# AdaptI2C-RF.net
KiCad netlist of a schematic drawn in EAGLE
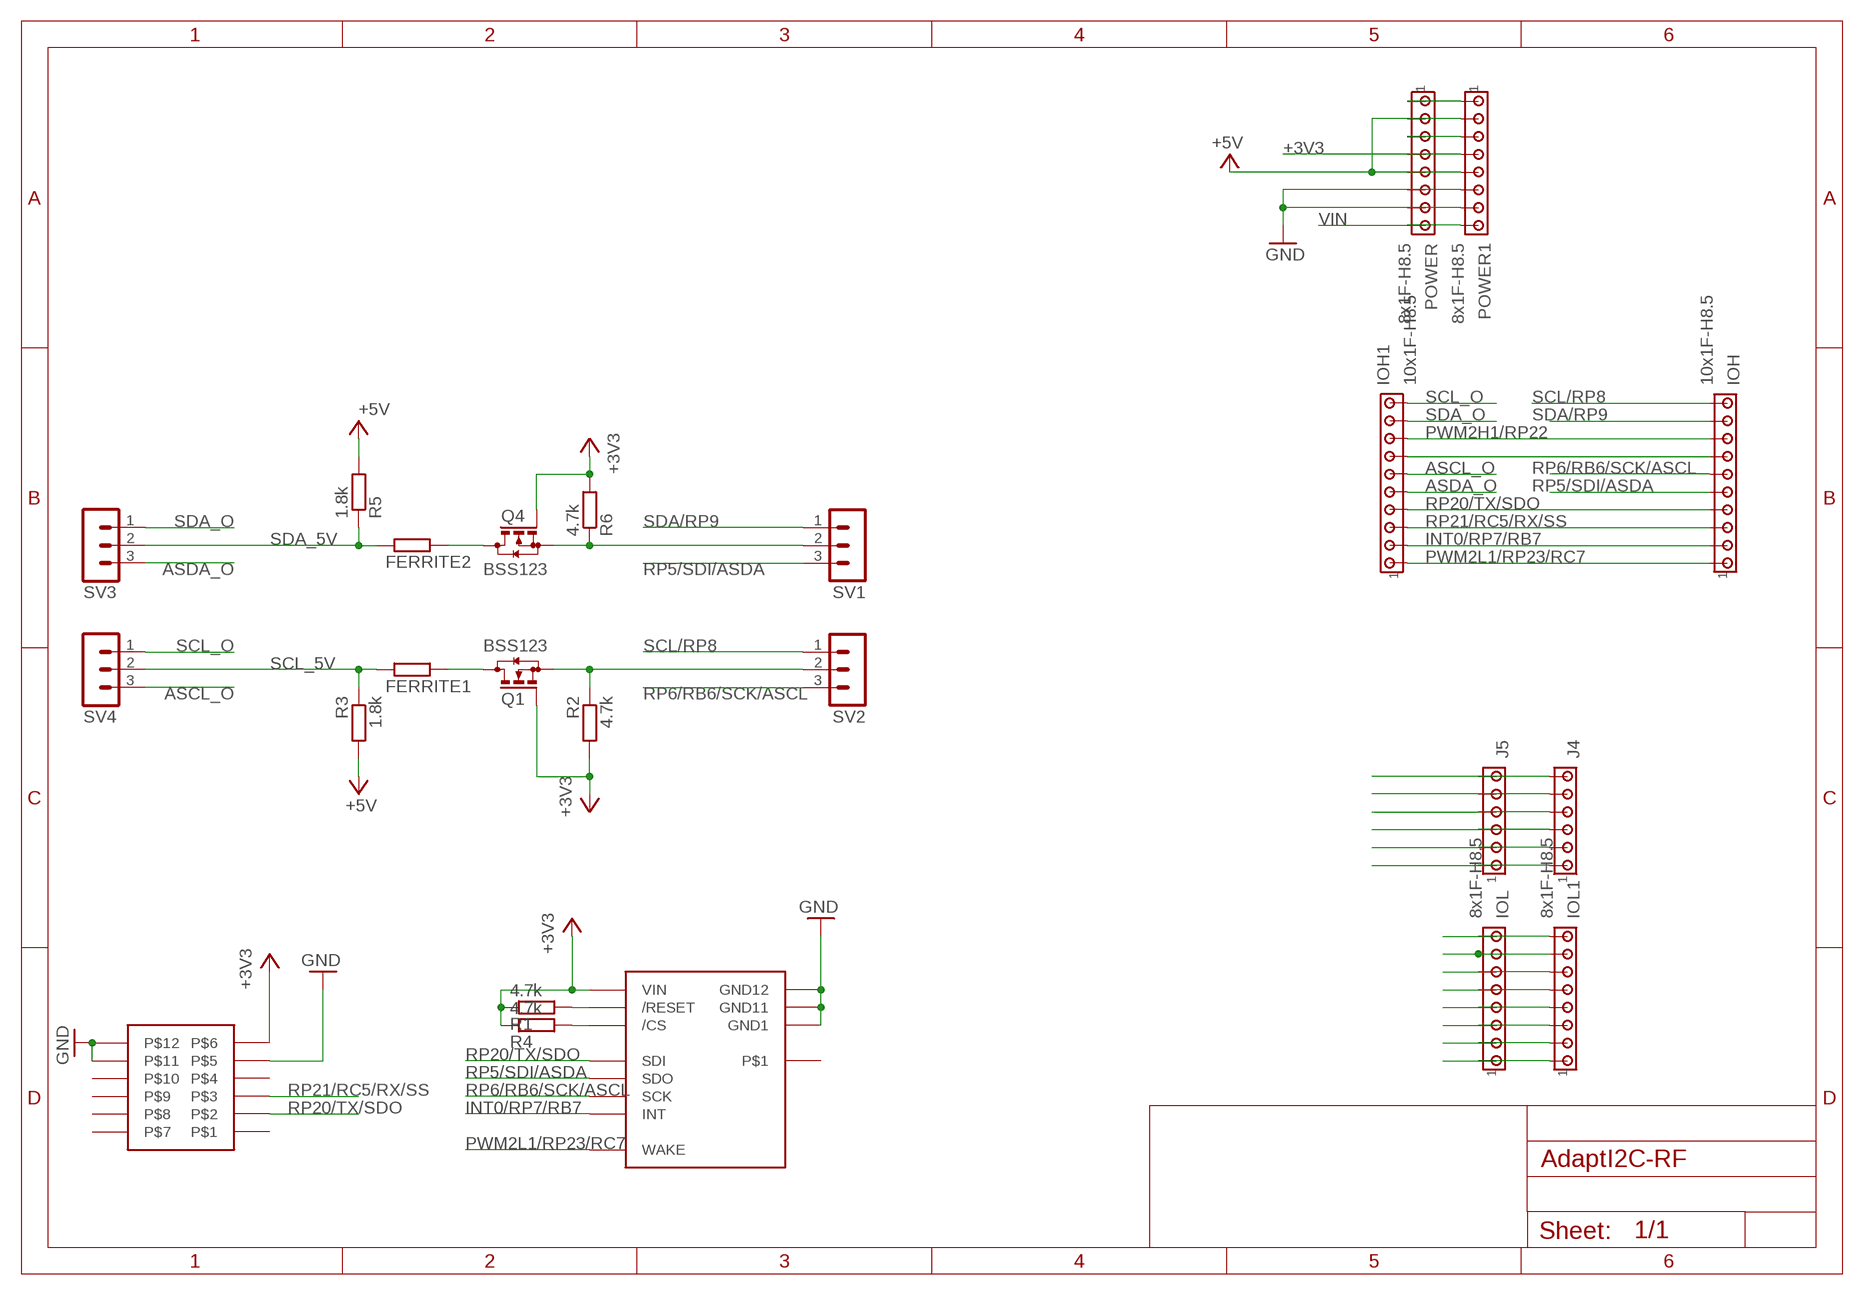
[diagram p0: schematic, sheet 1]

(export (version "E")
  (design (tool "Eeschema 10.0.6"))
  (components
    (comp (ref "FERRITE1")
      (value "R-EU_M0805")
      (footprint "eagle-import:M0805")
      (libsource (lib "eagle-import") (part "R-EU_M0805"))
    )
    (comp (ref "FERRITE2")
      (value "R-EU_M0805")
      (footprint "eagle-import:M0805")
      (libsource (lib "eagle-import") (part "R-EU_M0805"))
    )
    (comp (ref "IOH")
      (value "10x1F-H8.5")
      (footprint "eagle-import:10X10MTA")
      (libsource (lib "eagle-import") (part "MTA10-100"))
    )
    (comp (ref "IOH1")
      (value "10x1F-H8.5")
      (footprint "eagle-import:10X10MTA")
      (libsource (lib "eagle-import") (part "MTA10-100"))
    )
    (comp (ref "IOL")
      (value "8x1F-H8.5")
      (footprint "eagle-import:10X08MTA")
      (libsource (lib "eagle-import") (part "MTA08-100"))
    )
    (comp (ref "IOL1")
      (value "8x1F-H8.5")
      (footprint "eagle-import:10X08MTA")
      (libsource (lib "eagle-import") (part "MTA08-100"))
    )
    (comp (ref "J4")
      (value "MTA06-100")
      (footprint "eagle-import:10X06MTA")
      (libsource (lib "eagle-import") (part "MTA06-100"))
    )
    (comp (ref "J5")
      (value "MTA06-100")
      (footprint "eagle-import:10X06MTA")
      (libsource (lib "eagle-import") (part "MTA06-100"))
    )
    (comp (ref "POWER")
      (value "8x1F-H8.5")
      (footprint "eagle-import:10X08MTA")
      (libsource (lib "eagle-import") (part "MTA08-100"))
    )
    (comp (ref "POWER1")
      (value "8x1F-H8.5")
      (footprint "eagle-import:10X08MTA")
      (libsource (lib "eagle-import") (part "MTA08-100"))
    )
    (comp (ref "Q1")
      (value "BSS123")
      (footprint "eagle-import:SOT23")
      (libsource (lib "eagle-import") (part "BSS123"))
    )
    (comp (ref "Q4")
      (value "BSS123")
      (footprint "eagle-import:SOT23")
      (libsource (lib "eagle-import") (part "BSS123"))
    )
    (comp (ref "R1")
      (value "4.7k")
      (footprint "eagle-import:R0805")
      (libsource (lib "eagle-import") (part "rcl_R-EU_R0805"))
    )
    (comp (ref "R2")
      (value "4.7k")
      (footprint "eagle-import:R0805")
      (libsource (lib "eagle-import") (part "rcl_R-EU_R0805"))
    )
    (comp (ref "R3")
      (value "1.8k")
      (footprint "eagle-import:0204_7")
      (libsource (lib "eagle-import") (part "rcl_R-EU_0204/7"))
    )
    (comp (ref "R4")
      (value "4.7k")
      (footprint "eagle-import:R0805")
      (libsource (lib "eagle-import") (part "rcl_R-EU_R0805"))
    )
    (comp (ref "R5")
      (value "1.8k")
      (footprint "eagle-import:0204_7")
      (libsource (lib "eagle-import") (part "rcl_R-EU_0204/7"))
    )
    (comp (ref "R6")
      (value "4.7k")
      (footprint "eagle-import:R0805")
      (libsource (lib "eagle-import") (part "rcl_R-EU_R0805"))
    )
    (comp (ref "SV1")
      (value "MA03-1")
      (footprint "eagle-import:MA03-1")
      (libsource (lib "eagle-import") (part "MA03-1"))
    )
    (comp (ref "SV2")
      (value "MA03-1")
      (footprint "eagle-import:MA03-1")
      (libsource (lib "eagle-import") (part "MA03-1"))
    )
    (comp (ref "SV3")
      (value "MA03-1")
      (footprint "eagle-import:MA03-1")
      (libsource (lib "eagle-import") (part "MA03-1"))
    )
    (comp (ref "SV4")
      (value "MA03-1")
      (footprint "eagle-import:MA03-1")
      (libsource (lib "eagle-import") (part "MA03-1"))
    )
    (comp (ref "U$2")
      (value "MRF24J40MA")
      (footprint "eagle-import:MRF24J40MA")
      (libsource (lib "eagle-import") (part "MRF24J40MA"))
    )
    (comp (ref "U$7")
      (value "PMOD2X6")
      (footprint "eagle-import:PMOD2X6")
      (libsource (lib "eagle-import") (part "PMOD2X6"))
    )
  )
  (nets
    (net (code "1") (name "+3V3") (class "Default")
      (node (ref "POWER") (pin "4") (pinfunction "4_4") (pintype "passive"))
      (node (ref "POWER1") (pin "4") (pinfunction "4_4") (pintype "passive"))
      (node (ref "Q1") (pin "1") (pinfunction "G_1") (pintype "passive"))
      (node (ref "Q4") (pin "1") (pinfunction "G_1") (pintype "passive"))
      (node (ref "R1") (pin "1") (pinfunction "1_1") (pintype "passive"))
      (node (ref "R2") (pin "2") (pinfunction "2_2") (pintype "passive"))
      (node (ref "R4") (pin "1") (pinfunction "1_1") (pintype "passive"))
      (node (ref "R6") (pin "2") (pinfunction "2_2") (pintype "passive"))
      (node (ref "U$2") (pin "P$10") (pinfunction "VIN_P$10") (pintype "power_in"))
      (node (ref "U$7") (pin "P$6") (pinfunction "P$6_P$6") (pintype "bidirectional"))
    )
    (net (code "2") (name "+5V") (class "Default")
      (node (ref "POWER") (pin "2") (pinfunction "2_2") (pintype "passive"))
      (node (ref "POWER") (pin "5") (pinfunction "5_5") (pintype "passive"))
      (node (ref "POWER1") (pin "2") (pinfunction "2_2") (pintype "passive"))
      (node (ref "POWER1") (pin "5") (pinfunction "5_5") (pintype "passive"))
      (node (ref "R3") (pin "2") (pinfunction "2_2") (pintype "passive"))
      (node (ref "R5") (pin "2") (pinfunction "2_2") (pintype "passive"))
    )
    (net (code "3") (name "/ASCL_O") (class "Default")
      (node (ref "IOH1") (pin "6") (pinfunction "6_6") (pintype "passive"))
      (node (ref "SV4") (pin "3") (pinfunction "3_3") (pintype "passive"))
    )
    (net (code "4") (name "/ASDA_O") (class "Default")
      (node (ref "IOH1") (pin "5") (pinfunction "5_5") (pintype "passive"))
      (node (ref "SV3") (pin "3") (pinfunction "3_3") (pintype "passive"))
    )
    (net (code "5") (name "/INT0{slash}RP7{slash}RB7") (class "Default")
      (node (ref "IOH") (pin "2") (pinfunction "2_2") (pintype "passive"))
      (node (ref "IOH1") (pin "2") (pinfunction "2_2") (pintype "passive"))
      (node (ref "U$2") (pin "P$4") (pinfunction "INT_P$4") (pintype "output"))
    )
    (net (code "6") (name "/PWM2H1{slash}RP22") (class "Default")
      (node (ref "IOH") (pin "8") (pinfunction "8_8") (pintype "passive"))
      (node (ref "IOH1") (pin "8") (pinfunction "8_8") (pintype "passive"))
    )
    (net (code "7") (name "/PWM2L1{slash}RP23{slash}RC7") (class "Default")
      (node (ref "IOH") (pin "1") (pinfunction "1_1") (pintype "passive"))
      (node (ref "IOH1") (pin "1") (pinfunction "1_1") (pintype "passive"))
      (node (ref "U$2") (pin "P$3") (pinfunction "WAKE_P$3") (pintype "input"))
    )
    (net (code "8") (name "/RP5{slash}SDI{slash}ASDA") (class "Default")
      (node (ref "IOH") (pin "5") (pinfunction "5_5") (pintype "passive"))
      (node (ref "SV1") (pin "3") (pinfunction "3_3") (pintype "passive"))
      (node (ref "U$2") (pin "P$7") (pinfunction "SDO_P$7") (pintype "output"))
    )
    (net (code "9") (name "/RP6{slash}RB6{slash}SCK{slash}ASCL") (class "Default")
      (node (ref "IOH") (pin "6") (pinfunction "6_6") (pintype "passive"))
      (node (ref "SV2") (pin "3") (pinfunction "3_3") (pintype "passive"))
      (node (ref "U$2") (pin "P$6") (pinfunction "SCK_P$6") (pintype "input"))
    )
    (net (code "10") (name "/RP20{slash}TX{slash}SDO") (class "Default")
      (node (ref "IOH") (pin "4") (pinfunction "4_4") (pintype "passive"))
      (node (ref "IOH1") (pin "4") (pinfunction "4_4") (pintype "passive"))
      (node (ref "U$2") (pin "P$5") (pinfunction "SDI_P$5") (pintype "input"))
      (node (ref "U$7") (pin "P$2") (pinfunction "P$2_P$2") (pintype "bidirectional"))
    )
    (net (code "11") (name "/RP21{slash}RC5{slash}RX{slash}SS") (class "Default")
      (node (ref "IOH") (pin "3") (pinfunction "3_3") (pintype "passive"))
      (node (ref "IOH1") (pin "3") (pinfunction "3_3") (pintype "passive"))
      (node (ref "R4") (pin "2") (pinfunction "2_2") (pintype "passive"))
      (node (ref "U$2") (pin "P$8") (pinfunction "/CS_P$8") (pintype "input"))
      (node (ref "U$7") (pin "P$3") (pinfunction "P$3_P$3") (pintype "bidirectional"))
    )
    (net (code "12") (name "/SCL_5V") (class "Default")
      (node (ref "FERRITE1") (pin "1") (pinfunction "1_1") (pintype "passive"))
      (node (ref "R3") (pin "1") (pinfunction "1_1") (pintype "passive"))
      (node (ref "SV4") (pin "2") (pinfunction "2_2") (pintype "passive"))
    )
    (net (code "13") (name "/SCL_O") (class "Default")
      (node (ref "IOH1") (pin "10") (pinfunction "10_10") (pintype "passive"))
      (node (ref "SV4") (pin "1") (pinfunction "1_1") (pintype "passive"))
    )
    (net (code "14") (name "/SCL{slash}RP8") (class "Default")
      (node (ref "IOH") (pin "10") (pinfunction "10_10") (pintype "passive"))
      (node (ref "SV2") (pin "1") (pinfunction "1_1") (pintype "passive"))
    )
    (net (code "15") (name "/SDA_5V") (class "Default")
      (node (ref "FERRITE2") (pin "1") (pinfunction "1_1") (pintype "passive"))
      (node (ref "R5") (pin "1") (pinfunction "1_1") (pintype "passive"))
      (node (ref "SV3") (pin "2") (pinfunction "2_2") (pintype "passive"))
    )
    (net (code "16") (name "/SDA_O") (class "Default")
      (node (ref "IOH1") (pin "9") (pinfunction "9_9") (pintype "passive"))
      (node (ref "SV3") (pin "1") (pinfunction "1_1") (pintype "passive"))
    )
    (net (code "17") (name "/SDA{slash}RP9") (class "Default")
      (node (ref "IOH") (pin "9") (pinfunction "9_9") (pintype "passive"))
      (node (ref "SV1") (pin "1") (pinfunction "1_1") (pintype "passive"))
    )
    (net (code "18") (name "/VIN") (class "Default")
      (node (ref "POWER") (pin "8") (pinfunction "8_8") (pintype "passive"))
      (node (ref "POWER1") (pin "8") (pinfunction "8_8") (pintype "passive"))
    )
    (net (code "19") (name "GND") (class "Default")
      (node (ref "POWER") (pin "6") (pinfunction "6_6") (pintype "passive"))
      (node (ref "POWER") (pin "7") (pinfunction "7_7") (pintype "passive"))
      (node (ref "POWER1") (pin "6") (pinfunction "6_6") (pintype "passive"))
      (node (ref "POWER1") (pin "7") (pinfunction "7_7") (pintype "passive"))
      (node (ref "U$2") (pin "P$1") (pinfunction "GND1_P$1") (pintype "power_in"))
      (node (ref "U$2") (pin "P$11") (pinfunction "GND11_P$11") (pintype "power_in"))
      (node (ref "U$2") (pin "P$12") (pinfunction "GND12_P$12") (pintype "power_in"))
      (node (ref "U$7") (pin "P$11") (pinfunction "P$11_P$11") (pintype "bidirectional"))
      (node (ref "U$7") (pin "P$12") (pinfunction "P$12_P$12") (pintype "bidirectional"))
      (node (ref "U$7") (pin "P$5") (pinfunction "P$5_P$5") (pintype "bidirectional"))
    )
    (net (code "20") (name "Net-(IOH-Pad7)") (class "Default")
      (node (ref "IOH") (pin "7") (pinfunction "7_7") (pintype "passive"))
      (node (ref "IOH1") (pin "7") (pinfunction "7_7") (pintype "passive"))
    )
    (net (code "21") (name "Net-(IOL-Pad1)") (class "Default")
      (node (ref "IOL") (pin "1") (pinfunction "1_1") (pintype "passive"))
      (node (ref "IOL1") (pin "1") (pinfunction "1_1") (pintype "passive"))
    )
    (net (code "22") (name "Net-(IOL-Pad2)") (class "Default")
      (node (ref "IOL") (pin "2") (pinfunction "2_2") (pintype "passive"))
      (node (ref "IOL1") (pin "2") (pinfunction "2_2") (pintype "passive"))
    )
    (net (code "23") (name "Net-(IOL-Pad3)") (class "Default")
      (node (ref "IOL") (pin "3") (pinfunction "3_3") (pintype "passive"))
      (node (ref "IOL1") (pin "3") (pinfunction "3_3") (pintype "passive"))
    )
    (net (code "24") (name "Net-(IOL-Pad4)") (class "Default")
      (node (ref "IOL") (pin "4") (pinfunction "4_4") (pintype "passive"))
      (node (ref "IOL1") (pin "4") (pinfunction "4_4") (pintype "passive"))
    )
    (net (code "25") (name "Net-(IOL-Pad5)") (class "Default")
      (node (ref "IOL") (pin "5") (pinfunction "5_5") (pintype "passive"))
      (node (ref "IOL1") (pin "5") (pinfunction "5_5") (pintype "passive"))
    )
    (net (code "26") (name "Net-(IOL-Pad6)") (class "Default")
      (node (ref "IOL") (pin "6") (pinfunction "6_6") (pintype "passive"))
      (node (ref "IOL1") (pin "6") (pinfunction "6_6") (pintype "passive"))
    )
    (net (code "27") (name "Net-(IOL-Pad7)") (class "Default")
      (node (ref "IOL") (pin "7") (pinfunction "7_7") (pintype "passive"))
      (node (ref "IOL1") (pin "7") (pinfunction "7_7") (pintype "passive"))
    )
    (net (code "28") (name "Net-(IOL-Pad8)") (class "Default")
      (node (ref "IOL") (pin "8") (pinfunction "8_8") (pintype "passive"))
      (node (ref "IOL1") (pin "8") (pinfunction "8_8") (pintype "passive"))
    )
    (net (code "29") (name "Net-(J4-1)") (class "Default")
      (node (ref "J4") (pin "6") (pinfunction "1_6") (pintype "passive"))
      (node (ref "J5") (pin "6") (pinfunction "1_6") (pintype "passive"))
    )
    (net (code "30") (name "Net-(J4-2)") (class "Default")
      (node (ref "J4") (pin "5") (pinfunction "2_5") (pintype "passive"))
      (node (ref "J5") (pin "5") (pinfunction "2_5") (pintype "passive"))
    )
    (net (code "31") (name "Net-(J4-3)") (class "Default")
      (node (ref "J4") (pin "4") (pinfunction "3_4") (pintype "passive"))
      (node (ref "J5") (pin "4") (pinfunction "3_4") (pintype "passive"))
    )
    (net (code "32") (name "Net-(J4-4)") (class "Default")
      (node (ref "J4") (pin "3") (pinfunction "4_3") (pintype "passive"))
      (node (ref "J5") (pin "3") (pinfunction "4_3") (pintype "passive"))
    )
    (net (code "33") (name "Net-(J4-5)") (class "Default")
      (node (ref "J4") (pin "2") (pinfunction "5_2") (pintype "passive"))
      (node (ref "J5") (pin "2") (pinfunction "5_2") (pintype "passive"))
    )
    (net (code "34") (name "Net-(J4-6)") (class "Default")
      (node (ref "J4") (pin "1") (pinfunction "6_1") (pintype "passive"))
      (node (ref "J5") (pin "1") (pinfunction "6_1") (pintype "passive"))
    )
    (net (code "35") (name "Net-(POWER-Pad1)") (class "Default")
      (node (ref "POWER") (pin "1") (pinfunction "1_1") (pintype "passive"))
      (node (ref "POWER1") (pin "1") (pinfunction "1_1") (pintype "passive"))
    )
    (net (code "36") (name "Net-(POWER-Pad3)") (class "Default")
      (node (ref "POWER") (pin "3") (pinfunction "3_3") (pintype "passive"))
      (node (ref "POWER1") (pin "3") (pinfunction "3_3") (pintype "passive"))
    )
    (net (code "37") (name "Net-(Q1-D)") (class "Default")
      (node (ref "FERRITE1") (pin "2") (pinfunction "2_2") (pintype "passive"))
      (node (ref "Q1") (pin "3") (pinfunction "D_3") (pintype "passive"))
    )
    (net (code "38") (name "Net-(Q1-S)") (class "Default")
      (node (ref "Q1") (pin "2") (pinfunction "S_2") (pintype "passive"))
      (node (ref "R2") (pin "1") (pinfunction "1_1") (pintype "passive"))
      (node (ref "SV2") (pin "2") (pinfunction "2_2") (pintype "passive"))
    )
    (net (code "39") (name "Net-(Q4-D)") (class "Default")
      (node (ref "FERRITE2") (pin "2") (pinfunction "2_2") (pintype "passive"))
      (node (ref "Q4") (pin "3") (pinfunction "D_3") (pintype "passive"))
    )
    (net (code "40") (name "Net-(Q4-S)") (class "Default")
      (node (ref "Q4") (pin "2") (pinfunction "S_2") (pintype "passive"))
      (node (ref "R6") (pin "1") (pinfunction "1_1") (pintype "passive"))
      (node (ref "SV1") (pin "2") (pinfunction "2_2") (pintype "passive"))
    )
    (net (code "41") (name "Net-(U$2-{slash}RESET)") (class "Default")
      (node (ref "R1") (pin "2") (pinfunction "2_2") (pintype "passive"))
      (node (ref "U$2") (pin "P$2") (pinfunction "/RESET_P$2") (pintype "input"))
    )
    (net (code "42") (name "unconnected-(U$2-P$1-PadP$9)") (class "Default")
      (node (ref "U$2") (pin "P$9") (pinfunction "P$1_P$9") (pintype "no_connect"))
    )
    (net (code "43") (name "unconnected-(U$7-PadP$1)") (class "Default")
      (node (ref "U$7") (pin "P$1") (pinfunction "P$1_P$1") (pintype "bidirectional"))
    )
    (net (code "44") (name "unconnected-(U$7-PadP$4)") (class "Default")
      (node (ref "U$7") (pin "P$4") (pinfunction "P$4_P$4") (pintype "bidirectional"))
    )
    (net (code "45") (name "unconnected-(U$7-PadP$7)") (class "Default")
      (node (ref "U$7") (pin "P$7") (pinfunction "P$7_P$7") (pintype "bidirectional"))
    )
    (net (code "46") (name "unconnected-(U$7-PadP$8)") (class "Default")
      (node (ref "U$7") (pin "P$8") (pinfunction "P$8_P$8") (pintype "bidirectional"))
    )
    (net (code "47") (name "unconnected-(U$7-PadP$9)") (class "Default")
      (node (ref "U$7") (pin "P$9") (pinfunction "P$9_P$9") (pintype "bidirectional"))
    )
    (net (code "48") (name "unconnected-(U$7-PadP$10)") (class "Default")
      (node (ref "U$7") (pin "P$10") (pinfunction "P$10_P$10") (pintype "bidirectional"))
    )
  )
)
